# 08_DDR3L_Modules.net
KiCad netlist of a schematic drawn in Altium Designer
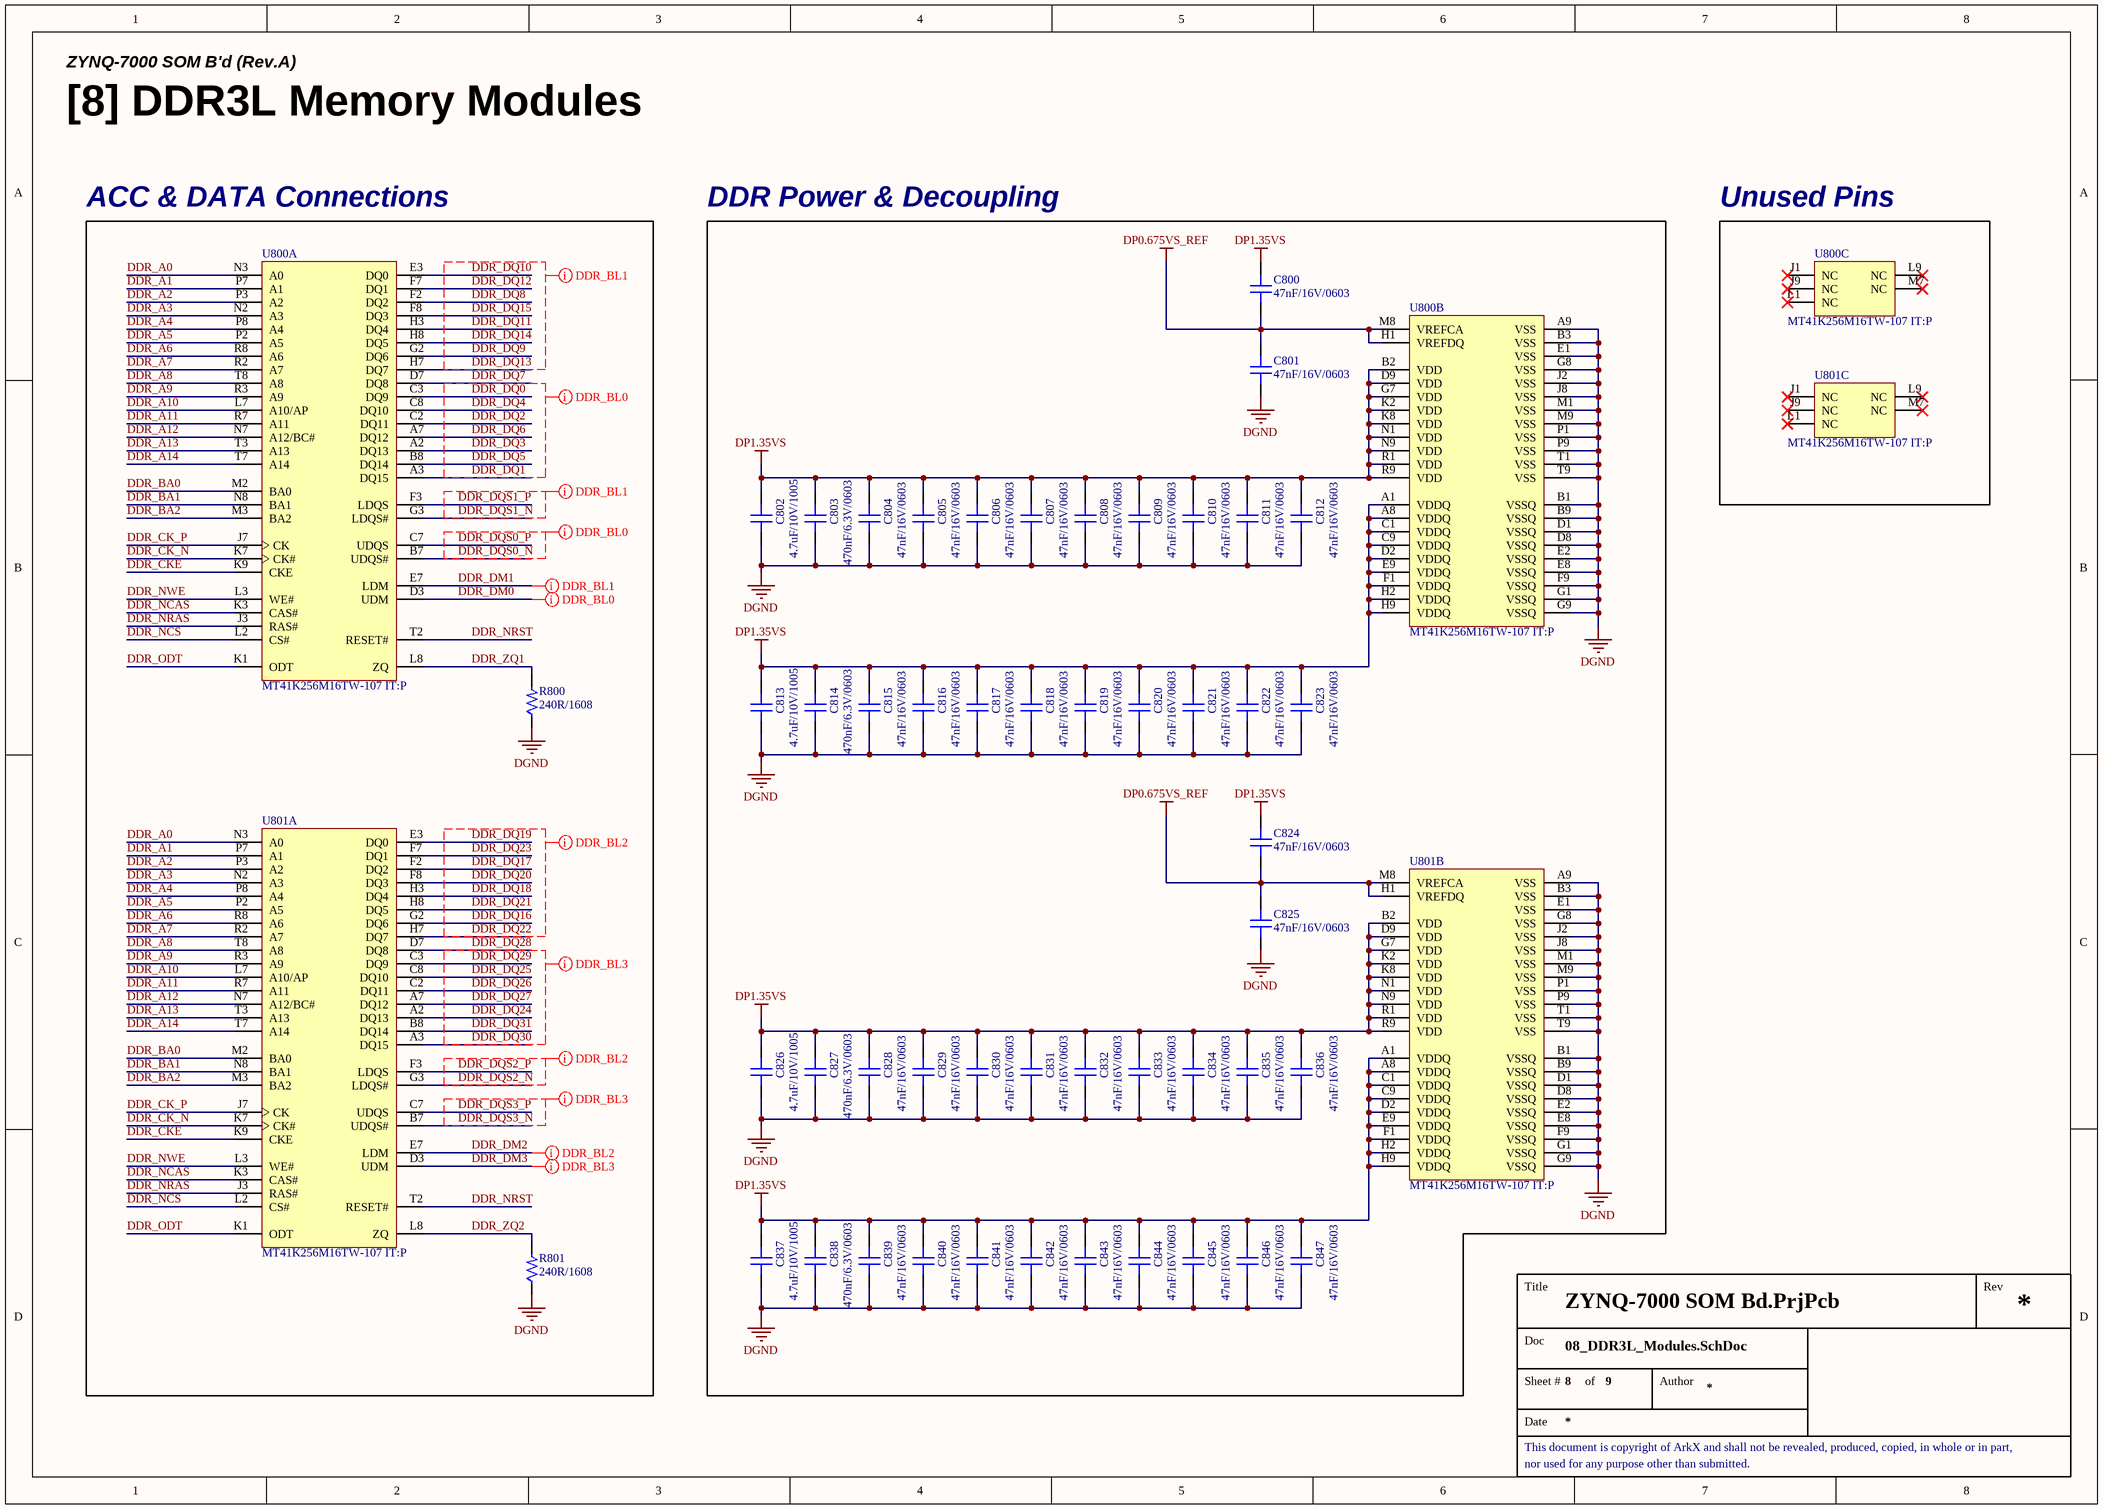
[diagram p0: 08_DDR3L_Modules.SchDoc]

(export (version "E")
  (design (tool "Eeschema 10.0.6"))
  (components
    (comp (ref "C800")
      (value "47nF/16V/0603")
      (footprint "CAP 0603 (0201_INCH)")
      (description "16V 47nF X5R ±10% 0201 Multilayer Ceramic Capacitors MLCC - SMD/SMT ROHS")
      (fields (field (name "LCSC PART #") "C88917"))
      (libsource (lib "Arkx") (part "CAP_47nF/16V/0603"))
    )
    (comp (ref "C801")
      (value "47nF/16V/0603")
      (footprint "CAP 0603 (0201_INCH)")
      (description "16V 47nF X5R ±10% 0201 Multilayer Ceramic Capacitors MLCC - SMD/SMT ROHS")
      (fields (field (name "LCSC PART #") "C88917"))
      (libsource (lib "Arkx") (part "CAP_47nF/16V/0603"))
    )
    (comp (ref "C802")
      (value "4.7uF/10V/1005")
      (footprint "CAP 1005 (0402_INCH)")
      (description "10V 4.7uF X5R ±20% 0402  Multilayer Ceramic Capacitors MLCC - SMD/SMT ROHS")
      (fields (field (name "LCSC PART #") "C23733"))
      (libsource (lib "Arkx") (part "CAP_4.7uF/10V/1005"))
    )
    (comp (ref "C803")
      (value "470nF/6.3V/0603")
      (footprint "CAP 0603 (0201_INCH)")
      (description "6.3V 470nF X5R ±10% 0201  Multilayer Ceramic Capacitors MLCC - SMD/SMT ROHS")
      (fields (field (name "LCSC PART #") "C85926"))
      (libsource (lib "Arkx") (part "CAP_470nF/6.3V/0603"))
    )
    (comp (ref "C804")
      (value "47nF/16V/0603")
      (footprint "CAP 0603 (0201_INCH)")
      (description "16V 47nF X5R ±10% 0201 Multilayer Ceramic Capacitors MLCC - SMD/SMT ROHS")
      (fields (field (name "LCSC PART #") "C88917"))
      (libsource (lib "Arkx") (part "CAP_47nF/16V/0603"))
    )
    (comp (ref "C805")
      (value "47nF/16V/0603")
      (footprint "CAP 0603 (0201_INCH)")
      (description "16V 47nF X5R ±10% 0201 Multilayer Ceramic Capacitors MLCC - SMD/SMT ROHS")
      (fields (field (name "LCSC PART #") "C88917"))
      (libsource (lib "Arkx") (part "CAP_47nF/16V/0603"))
    )
    (comp (ref "C806")
      (value "47nF/16V/0603")
      (footprint "CAP 0603 (0201_INCH)")
      (description "16V 47nF X5R ±10% 0201 Multilayer Ceramic Capacitors MLCC - SMD/SMT ROHS")
      (fields (field (name "LCSC PART #") "C88917"))
      (libsource (lib "Arkx") (part "CAP_47nF/16V/0603"))
    )
    (comp (ref "C807")
      (value "47nF/16V/0603")
      (footprint "CAP 0603 (0201_INCH)")
      (description "16V 47nF X5R ±10% 0201 Multilayer Ceramic Capacitors MLCC - SMD/SMT ROHS")
      (fields (field (name "LCSC PART #") "C88917"))
      (libsource (lib "Arkx") (part "CAP_47nF/16V/0603"))
    )
    (comp (ref "C808")
      (value "47nF/16V/0603")
      (footprint "CAP 0603 (0201_INCH)")
      (description "16V 47nF X5R ±10% 0201 Multilayer Ceramic Capacitors MLCC - SMD/SMT ROHS")
      (fields (field (name "LCSC PART #") "C88917"))
      (libsource (lib "Arkx") (part "CAP_47nF/16V/0603"))
    )
    (comp (ref "C809")
      (value "47nF/16V/0603")
      (footprint "CAP 0603 (0201_INCH)")
      (description "16V 47nF X5R ±10% 0201 Multilayer Ceramic Capacitors MLCC - SMD/SMT ROHS")
      (fields (field (name "LCSC PART #") "C88917"))
      (libsource (lib "Arkx") (part "CAP_47nF/16V/0603"))
    )
    (comp (ref "C810")
      (value "47nF/16V/0603")
      (footprint "CAP 0603 (0201_INCH)")
      (description "16V 47nF X5R ±10% 0201 Multilayer Ceramic Capacitors MLCC - SMD/SMT ROHS")
      (fields (field (name "LCSC PART #") "C88917"))
      (libsource (lib "Arkx") (part "CAP_47nF/16V/0603"))
    )
    (comp (ref "C811")
      (value "47nF/16V/0603")
      (footprint "CAP 0603 (0201_INCH)")
      (description "16V 47nF X5R ±10% 0201 Multilayer Ceramic Capacitors MLCC - SMD/SMT ROHS")
      (fields (field (name "LCSC PART #") "C88917"))
      (libsource (lib "Arkx") (part "CAP_47nF/16V/0603"))
    )
    (comp (ref "C812")
      (value "47nF/16V/0603")
      (footprint "CAP 0603 (0201_INCH)")
      (description "16V 47nF X5R ±10% 0201 Multilayer Ceramic Capacitors MLCC - SMD/SMT ROHS")
      (fields (field (name "LCSC PART #") "C88917"))
      (libsource (lib "Arkx") (part "CAP_47nF/16V/0603"))
    )
    (comp (ref "C813")
      (value "4.7uF/10V/1005")
      (footprint "CAP 1005 (0402_INCH)")
      (description "10V 4.7uF X5R ±20% 0402  Multilayer Ceramic Capacitors MLCC - SMD/SMT ROHS")
      (fields (field (name "LCSC PART #") "C23733"))
      (libsource (lib "Arkx") (part "CAP_4.7uF/10V/1005"))
    )
    (comp (ref "C814")
      (value "470nF/6.3V/0603")
      (footprint "CAP 0603 (0201_INCH)")
      (description "6.3V 470nF X5R ±10% 0201  Multilayer Ceramic Capacitors MLCC - SMD/SMT ROHS")
      (fields (field (name "LCSC PART #") "C85926"))
      (libsource (lib "Arkx") (part "CAP_470nF/6.3V/0603"))
    )
    (comp (ref "C815")
      (value "47nF/16V/0603")
      (footprint "CAP 0603 (0201_INCH)")
      (description "16V 47nF X5R ±10% 0201 Multilayer Ceramic Capacitors MLCC - SMD/SMT ROHS")
      (fields (field (name "LCSC PART #") "C88917"))
      (libsource (lib "Arkx") (part "CAP_47nF/16V/0603"))
    )
    (comp (ref "C816")
      (value "47nF/16V/0603")
      (footprint "CAP 0603 (0201_INCH)")
      (description "16V 47nF X5R ±10% 0201 Multilayer Ceramic Capacitors MLCC - SMD/SMT ROHS")
      (fields (field (name "LCSC PART #") "C88917"))
      (libsource (lib "Arkx") (part "CAP_47nF/16V/0603"))
    )
    (comp (ref "C817")
      (value "47nF/16V/0603")
      (footprint "CAP 0603 (0201_INCH)")
      (description "16V 47nF X5R ±10% 0201 Multilayer Ceramic Capacitors MLCC - SMD/SMT ROHS")
      (fields (field (name "LCSC PART #") "C88917"))
      (libsource (lib "Arkx") (part "CAP_47nF/16V/0603"))
    )
    (comp (ref "C818")
      (value "47nF/16V/0603")
      (footprint "CAP 0603 (0201_INCH)")
      (description "16V 47nF X5R ±10% 0201 Multilayer Ceramic Capacitors MLCC - SMD/SMT ROHS")
      (fields (field (name "LCSC PART #") "C88917"))
      (libsource (lib "Arkx") (part "CAP_47nF/16V/0603"))
    )
    (comp (ref "C819")
      (value "47nF/16V/0603")
      (footprint "CAP 0603 (0201_INCH)")
      (description "16V 47nF X5R ±10% 0201 Multilayer Ceramic Capacitors MLCC - SMD/SMT ROHS")
      (fields (field (name "LCSC PART #") "C88917"))
      (libsource (lib "Arkx") (part "CAP_47nF/16V/0603"))
    )
    (comp (ref "C820")
      (value "47nF/16V/0603")
      (footprint "CAP 0603 (0201_INCH)")
      (description "16V 47nF X5R ±10% 0201 Multilayer Ceramic Capacitors MLCC - SMD/SMT ROHS")
      (fields (field (name "LCSC PART #") "C88917"))
      (libsource (lib "Arkx") (part "CAP_47nF/16V/0603"))
    )
    (comp (ref "C821")
      (value "47nF/16V/0603")
      (footprint "CAP 0603 (0201_INCH)")
      (description "16V 47nF X5R ±10% 0201 Multilayer Ceramic Capacitors MLCC - SMD/SMT ROHS")
      (fields (field (name "LCSC PART #") "C88917"))
      (libsource (lib "Arkx") (part "CAP_47nF/16V/0603"))
    )
    (comp (ref "C822")
      (value "47nF/16V/0603")
      (footprint "CAP 0603 (0201_INCH)")
      (description "16V 47nF X5R ±10% 0201 Multilayer Ceramic Capacitors MLCC - SMD/SMT ROHS")
      (fields (field (name "LCSC PART #") "C88917"))
      (libsource (lib "Arkx") (part "CAP_47nF/16V/0603"))
    )
    (comp (ref "C823")
      (value "47nF/16V/0603")
      (footprint "CAP 0603 (0201_INCH)")
      (description "16V 47nF X5R ±10% 0201 Multilayer Ceramic Capacitors MLCC - SMD/SMT ROHS")
      (fields (field (name "LCSC PART #") "C88917"))
      (libsource (lib "Arkx") (part "CAP_47nF/16V/0603"))
    )
    (comp (ref "C824")
      (value "47nF/16V/0603")
      (footprint "CAP 0603 (0201_INCH)")
      (description "16V 47nF X5R ±10% 0201 Multilayer Ceramic Capacitors MLCC - SMD/SMT ROHS")
      (fields (field (name "LCSC PART #") "C88917"))
      (libsource (lib "Arkx") (part "CAP_47nF/16V/0603"))
    )
    (comp (ref "C825")
      (value "47nF/16V/0603")
      (footprint "CAP 0603 (0201_INCH)")
      (description "16V 47nF X5R ±10% 0201 Multilayer Ceramic Capacitors MLCC - SMD/SMT ROHS")
      (fields (field (name "LCSC PART #") "C88917"))
      (libsource (lib "Arkx") (part "CAP_47nF/16V/0603"))
    )
    (comp (ref "C826")
      (value "4.7uF/10V/1005")
      (footprint "CAP 1005 (0402_INCH)")
      (description "10V 4.7uF X5R ±20% 0402  Multilayer Ceramic Capacitors MLCC - SMD/SMT ROHS")
      (fields (field (name "LCSC PART #") "C23733"))
      (libsource (lib "Arkx") (part "CAP_4.7uF/10V/1005"))
    )
    (comp (ref "C827")
      (value "470nF/6.3V/0603")
      (footprint "CAP 0603 (0201_INCH)")
      (description "6.3V 470nF X5R ±10% 0201  Multilayer Ceramic Capacitors MLCC - SMD/SMT ROHS")
      (fields (field (name "LCSC PART #") "C85926"))
      (libsource (lib "Arkx") (part "CAP_470nF/6.3V/0603"))
    )
    (comp (ref "C828")
      (value "47nF/16V/0603")
      (footprint "CAP 0603 (0201_INCH)")
      (description "16V 47nF X5R ±10% 0201 Multilayer Ceramic Capacitors MLCC - SMD/SMT ROHS")
      (fields (field (name "LCSC PART #") "C88917"))
      (libsource (lib "Arkx") (part "CAP_47nF/16V/0603"))
    )
    (comp (ref "C829")
      (value "47nF/16V/0603")
      (footprint "CAP 0603 (0201_INCH)")
      (description "16V 47nF X5R ±10% 0201 Multilayer Ceramic Capacitors MLCC - SMD/SMT ROHS")
      (fields (field (name "LCSC PART #") "C88917"))
      (libsource (lib "Arkx") (part "CAP_47nF/16V/0603"))
    )
    (comp (ref "C830")
      (value "47nF/16V/0603")
      (footprint "CAP 0603 (0201_INCH)")
      (description "16V 47nF X5R ±10% 0201 Multilayer Ceramic Capacitors MLCC - SMD/SMT ROHS")
      (fields (field (name "LCSC PART #") "C88917"))
      (libsource (lib "Arkx") (part "CAP_47nF/16V/0603"))
    )
    (comp (ref "C831")
      (value "47nF/16V/0603")
      (footprint "CAP 0603 (0201_INCH)")
      (description "16V 47nF X5R ±10% 0201 Multilayer Ceramic Capacitors MLCC - SMD/SMT ROHS")
      (fields (field (name "LCSC PART #") "C88917"))
      (libsource (lib "Arkx") (part "CAP_47nF/16V/0603"))
    )
    (comp (ref "C832")
      (value "47nF/16V/0603")
      (footprint "CAP 0603 (0201_INCH)")
      (description "16V 47nF X5R ±10% 0201 Multilayer Ceramic Capacitors MLCC - SMD/SMT ROHS")
      (fields (field (name "LCSC PART #") "C88917"))
      (libsource (lib "Arkx") (part "CAP_47nF/16V/0603"))
    )
    (comp (ref "C833")
      (value "47nF/16V/0603")
      (footprint "CAP 0603 (0201_INCH)")
      (description "16V 47nF X5R ±10% 0201 Multilayer Ceramic Capacitors MLCC - SMD/SMT ROHS")
      (fields (field (name "LCSC PART #") "C88917"))
      (libsource (lib "Arkx") (part "CAP_47nF/16V/0603"))
    )
    (comp (ref "C834")
      (value "47nF/16V/0603")
      (footprint "CAP 0603 (0201_INCH)")
      (description "16V 47nF X5R ±10% 0201 Multilayer Ceramic Capacitors MLCC - SMD/SMT ROHS")
      (fields (field (name "LCSC PART #") "C88917"))
      (libsource (lib "Arkx") (part "CAP_47nF/16V/0603"))
    )
    (comp (ref "C835")
      (value "47nF/16V/0603")
      (footprint "CAP 0603 (0201_INCH)")
      (description "16V 47nF X5R ±10% 0201 Multilayer Ceramic Capacitors MLCC - SMD/SMT ROHS")
      (fields (field (name "LCSC PART #") "C88917"))
      (libsource (lib "Arkx") (part "CAP_47nF/16V/0603"))
    )
    (comp (ref "C836")
      (value "47nF/16V/0603")
      (footprint "CAP 0603 (0201_INCH)")
      (description "16V 47nF X5R ±10% 0201 Multilayer Ceramic Capacitors MLCC - SMD/SMT ROHS")
      (fields (field (name "LCSC PART #") "C88917"))
      (libsource (lib "Arkx") (part "CAP_47nF/16V/0603"))
    )
    (comp (ref "C837")
      (value "4.7uF/10V/1005")
      (footprint "CAP 1005 (0402_INCH)")
      (description "10V 4.7uF X5R ±20% 0402  Multilayer Ceramic Capacitors MLCC - SMD/SMT ROHS")
      (fields (field (name "LCSC PART #") "C23733"))
      (libsource (lib "Arkx") (part "CAP_4.7uF/10V/1005"))
    )
    (comp (ref "C838")
      (value "470nF/6.3V/0603")
      (footprint "CAP 0603 (0201_INCH)")
      (description "6.3V 470nF X5R ±10% 0201  Multilayer Ceramic Capacitors MLCC - SMD/SMT ROHS")
      (fields (field (name "LCSC PART #") "C85926"))
      (libsource (lib "Arkx") (part "CAP_470nF/6.3V/0603"))
    )
    (comp (ref "C839")
      (value "47nF/16V/0603")
      (footprint "CAP 0603 (0201_INCH)")
      (description "16V 47nF X5R ±10% 0201 Multilayer Ceramic Capacitors MLCC - SMD/SMT ROHS")
      (fields (field (name "LCSC PART #") "C88917"))
      (libsource (lib "Arkx") (part "CAP_47nF/16V/0603"))
    )
    (comp (ref "C840")
      (value "47nF/16V/0603")
      (footprint "CAP 0603 (0201_INCH)")
      (description "16V 47nF X5R ±10% 0201 Multilayer Ceramic Capacitors MLCC - SMD/SMT ROHS")
      (fields (field (name "LCSC PART #") "C88917"))
      (libsource (lib "Arkx") (part "CAP_47nF/16V/0603"))
    )
    (comp (ref "C841")
      (value "47nF/16V/0603")
      (footprint "CAP 0603 (0201_INCH)")
      (description "16V 47nF X5R ±10% 0201 Multilayer Ceramic Capacitors MLCC - SMD/SMT ROHS")
      (fields (field (name "LCSC PART #") "C88917"))
      (libsource (lib "Arkx") (part "CAP_47nF/16V/0603"))
    )
    (comp (ref "C842")
      (value "47nF/16V/0603")
      (footprint "CAP 0603 (0201_INCH)")
      (description "16V 47nF X5R ±10% 0201 Multilayer Ceramic Capacitors MLCC - SMD/SMT ROHS")
      (fields (field (name "LCSC PART #") "C88917"))
      (libsource (lib "Arkx") (part "CAP_47nF/16V/0603"))
    )
    (comp (ref "C843")
      (value "47nF/16V/0603")
      (footprint "CAP 0603 (0201_INCH)")
      (description "16V 47nF X5R ±10% 0201 Multilayer Ceramic Capacitors MLCC - SMD/SMT ROHS")
      (fields (field (name "LCSC PART #") "C88917"))
      (libsource (lib "Arkx") (part "CAP_47nF/16V/0603"))
    )
    (comp (ref "C844")
      (value "47nF/16V/0603")
      (footprint "CAP 0603 (0201_INCH)")
      (description "16V 47nF X5R ±10% 0201 Multilayer Ceramic Capacitors MLCC - SMD/SMT ROHS")
      (fields (field (name "LCSC PART #") "C88917"))
      (libsource (lib "Arkx") (part "CAP_47nF/16V/0603"))
    )
    (comp (ref "C845")
      (value "47nF/16V/0603")
      (footprint "CAP 0603 (0201_INCH)")
      (description "16V 47nF X5R ±10% 0201 Multilayer Ceramic Capacitors MLCC - SMD/SMT ROHS")
      (fields (field (name "LCSC PART #") "C88917"))
      (libsource (lib "Arkx") (part "CAP_47nF/16V/0603"))
    )
    (comp (ref "C846")
      (value "47nF/16V/0603")
      (footprint "CAP 0603 (0201_INCH)")
      (description "16V 47nF X5R ±10% 0201 Multilayer Ceramic Capacitors MLCC - SMD/SMT ROHS")
      (fields (field (name "LCSC PART #") "C88917"))
      (libsource (lib "Arkx") (part "CAP_47nF/16V/0603"))
    )
    (comp (ref "C847")
      (value "47nF/16V/0603")
      (footprint "CAP 0603 (0201_INCH)")
      (description "16V 47nF X5R ±10% 0201 Multilayer Ceramic Capacitors MLCC - SMD/SMT ROHS")
      (fields (field (name "LCSC PART #") "C88917"))
      (libsource (lib "Arkx") (part "CAP_47nF/16V/0603"))
    )
    (comp (ref "R800")
      (value "240R/1608")
      (footprint "RES 1608 (0603_inch)")
      (description "RES_240R/1608/0.1W")
      (fields (field (name "LCSC PART #") "C23350"))
      (libsource (lib "Arkx") (part "RES_240R/1608/0.1W"))
    )
    (comp (ref "R801")
      (value "240R/1608")
      (footprint "RES 1608 (0603_inch)")
      (description "RES_240R/1608/0.1W")
      (fields (field (name "LCSC PART #") "C23350"))
      (libsource (lib "Arkx") (part "RES_240R/1608/0.1W"))
    )
    (comp (ref "U800")
      (value "MT41K256M16TW-107 IT:P")
      (footprint "IC_MEM_DDR3L_MT41K256M16TW-107 IT:P")
      (description "SDRAM - DDR3L Memory IC 4Gbit Parallel 933 MHz 20 ns 96-FBGA (8x14)")
      (fields (field (name "LCSC PART #") "C367428"))
      (libsource (lib "Arkx") (part "IC_MEM_DDR3L_MT41K256M16TW-107 IT{colon}P"))
    )
    (comp (ref "U801")
      (value "MT41K256M16TW-107 IT:P")
      (footprint "IC_MEM_DDR3L_MT41K256M16TW-107 IT:P")
      (description "SDRAM - DDR3L Memory IC 4Gbit Parallel 933 MHz 20 ns 96-FBGA (8x14)")
      (fields (field (name "LCSC PART #") "C367428"))
      (libsource (lib "Arkx") (part "IC_MEM_DDR3L_MT41K256M16TW-107 IT{colon}P"))
    )
  )
  (nets
    (net (code "1") (name "/DDR_A0") (class "Default")
      (node (ref "U800") (pin "N3") (pinfunction "A0_N3") (pintype "passive"))
      (node (ref "U801") (pin "N3") (pinfunction "A0_N3") (pintype "passive"))
    )
    (net (code "2") (name "/DDR_A1") (class "Default")
      (node (ref "U800") (pin "P7") (pinfunction "A1_P7") (pintype "passive"))
      (node (ref "U801") (pin "P7") (pinfunction "A1_P7") (pintype "passive"))
    )
    (net (code "3") (name "/DDR_A2") (class "Default")
      (node (ref "U800") (pin "P3") (pinfunction "A2_P3") (pintype "passive"))
      (node (ref "U801") (pin "P3") (pinfunction "A2_P3") (pintype "passive"))
    )
    (net (code "4") (name "/DDR_A3") (class "Default")
      (node (ref "U800") (pin "N2") (pinfunction "A3_N2") (pintype "passive"))
      (node (ref "U801") (pin "N2") (pinfunction "A3_N2") (pintype "passive"))
    )
    (net (code "5") (name "/DDR_A4") (class "Default")
      (node (ref "U800") (pin "P8") (pinfunction "A4_P8") (pintype "passive"))
      (node (ref "U801") (pin "P8") (pinfunction "A4_P8") (pintype "passive"))
    )
    (net (code "6") (name "/DDR_A5") (class "Default")
      (node (ref "U800") (pin "P2") (pinfunction "A5_P2") (pintype "passive"))
      (node (ref "U801") (pin "P2") (pinfunction "A5_P2") (pintype "passive"))
    )
    (net (code "7") (name "/DDR_A6") (class "Default")
      (node (ref "U800") (pin "R8") (pinfunction "A6_R8") (pintype "passive"))
      (node (ref "U801") (pin "R8") (pinfunction "A6_R8") (pintype "passive"))
    )
    (net (code "8") (name "/DDR_A7") (class "Default")
      (node (ref "U800") (pin "R2") (pinfunction "A7_R2") (pintype "passive"))
      (node (ref "U801") (pin "R2") (pinfunction "A7_R2") (pintype "passive"))
    )
    (net (code "9") (name "/DDR_A8") (class "Default")
      (node (ref "U800") (pin "T8") (pinfunction "A8_T8") (pintype "passive"))
      (node (ref "U801") (pin "T8") (pinfunction "A8_T8") (pintype "passive"))
    )
    (net (code "10") (name "/DDR_A9") (class "Default")
      (node (ref "U800") (pin "R3") (pinfunction "A9_R3") (pintype "passive"))
      (node (ref "U801") (pin "R3") (pinfunction "A9_R3") (pintype "passive"))
    )
    (net (code "11") (name "/DDR_A10") (class "Default")
      (node (ref "U800") (pin "L7") (pinfunction "A10/AP_L7") (pintype "passive"))
      (node (ref "U801") (pin "L7") (pinfunction "A10/AP_L7") (pintype "passive"))
    )
    (net (code "12") (name "/DDR_A11") (class "Default")
      (node (ref "U800") (pin "R7") (pinfunction "A11_R7") (pintype "passive"))
      (node (ref "U801") (pin "R7") (pinfunction "A11_R7") (pintype "passive"))
    )
    (net (code "13") (name "/DDR_A12") (class "Default")
      (node (ref "U800") (pin "N7") (pinfunction "A12/BC#_N7") (pintype "passive"))
      (node (ref "U801") (pin "N7") (pinfunction "A12/BC#_N7") (pintype "passive"))
    )
    (net (code "14") (name "/DDR_A13") (class "Default")
      (node (ref "U800") (pin "T3") (pinfunction "A13_T3") (pintype "passive"))
      (node (ref "U801") (pin "T3") (pinfunction "A13_T3") (pintype "passive"))
    )
    (net (code "15") (name "/DDR_A14") (class "Default")
      (node (ref "U800") (pin "T7") (pinfunction "A14_T7") (pintype "passive"))
      (node (ref "U801") (pin "T7") (pinfunction "A14_T7") (pintype "passive"))
    )
    (net (code "16") (name "/DDR_BA0") (class "Default")
      (node (ref "U800") (pin "M2") (pinfunction "BA0_M2") (pintype "passive"))
      (node (ref "U801") (pin "M2") (pinfunction "BA0_M2") (pintype "passive"))
    )
    (net (code "17") (name "/DDR_BA1") (class "Default")
      (node (ref "U800") (pin "N8") (pinfunction "BA1_N8") (pintype "passive"))
      (node (ref "U801") (pin "N8") (pinfunction "BA1_N8") (pintype "passive"))
    )
    (net (code "18") (name "/DDR_BA2") (class "Default")
      (node (ref "U800") (pin "M3") (pinfunction "BA2_M3") (pintype "passive"))
      (node (ref "U801") (pin "M3") (pinfunction "BA2_M3") (pintype "passive"))
    )
    (net (code "19") (name "/DDR_CKE") (class "Default")
      (node (ref "U800") (pin "K9") (pinfunction "CKE_K9") (pintype "passive"))
      (node (ref "U801") (pin "K9") (pinfunction "CKE_K9") (pintype "passive"))
    )
    (net (code "20") (name "/DDR_CK_N") (class "Default")
      (node (ref "U800") (pin "K7") (pinfunction "CK#_K7") (pintype "passive"))
      (node (ref "U801") (pin "K7") (pinfunction "CK#_K7") (pintype "passive"))
    )
    (net (code "21") (name "/DDR_CK_P") (class "Default")
      (node (ref "U800") (pin "J7") (pinfunction "CK_J7") (pintype "passive"))
      (node (ref "U801") (pin "J7") (pinfunction "CK_J7") (pintype "passive"))
    )
    (net (code "22") (name "/DDR_DM0") (class "Default")
      (node (ref "U800") (pin "D3") (pinfunction "UDM_D3") (pintype "passive"))
    )
    (net (code "23") (name "/DDR_DM1") (class "Default")
      (node (ref "U800") (pin "E7") (pinfunction "LDM_E7") (pintype "passive"))
    )
    (net (code "24") (name "/DDR_DM2") (class "Default")
      (node (ref "U801") (pin "E7") (pinfunction "LDM_E7") (pintype "passive"))
    )
    (net (code "25") (name "/DDR_DM3") (class "Default")
      (node (ref "U801") (pin "D3") (pinfunction "UDM_D3") (pintype "passive"))
    )
    (net (code "26") (name "/DDR_DQ0") (class "Default")
      (node (ref "U800") (pin "C3") (pinfunction "DQ9_C3") (pintype "passive"))
    )
    (net (code "27") (name "/DDR_DQ1") (class "Default")
      (node (ref "U800") (pin "A3") (pinfunction "DQ15_A3") (pintype "passive"))
    )
    (net (code "28") (name "/DDR_DQ2") (class "Default")
      (node (ref "U800") (pin "C2") (pinfunction "DQ11_C2") (pintype "passive"))
    )
    (net (code "29") (name "/DDR_DQ3") (class "Default")
      (node (ref "U800") (pin "A2") (pinfunction "DQ13_A2") (pintype "passive"))
    )
    (net (code "30") (name "/DDR_DQ4") (class "Default")
      (node (ref "U800") (pin "C8") (pinfunction "DQ10_C8") (pintype "passive"))
    )
    (net (code "31") (name "/DDR_DQ5") (class "Default")
      (node (ref "U800") (pin "B8") (pinfunction "DQ14_B8") (pintype "passive"))
    )
    (net (code "32") (name "/DDR_DQ6") (class "Default")
      (node (ref "U800") (pin "A7") (pinfunction "DQ12_A7") (pintype "passive"))
    )
    (net (code "33") (name "/DDR_DQ7") (class "Default")
      (node (ref "U800") (pin "D7") (pinfunction "DQ8_D7") (pintype "passive"))
    )
    (net (code "34") (name "/DDR_DQ8") (class "Default")
      (node (ref "U800") (pin "F2") (pinfunction "DQ2_F2") (pintype "passive"))
    )
    (net (code "35") (name "/DDR_DQ9") (class "Default")
      (node (ref "U800") (pin "G2") (pinfunction "DQ6_G2") (pintype "passive"))
    )
    (net (code "36") (name "/DDR_DQ10") (class "Default")
      (node (ref "U800") (pin "E3") (pinfunction "DQ0_E3") (pintype "passive"))
    )
    (net (code "37") (name "/DDR_DQ11") (class "Default")
      (node (ref "U800") (pin "H3") (pinfunction "DQ4_H3") (pintype "passive"))
    )
    (net (code "38") (name "/DDR_DQ12") (class "Default")
      (node (ref "U800") (pin "F7") (pinfunction "DQ1_F7") (pintype "passive"))
    )
    (net (code "39") (name "/DDR_DQ13") (class "Default")
      (node (ref "U800") (pin "H7") (pinfunction "DQ7_H7") (pintype "passive"))
    )
    (net (code "40") (name "/DDR_DQ14") (class "Default")
      (node (ref "U800") (pin "H8") (pinfunction "DQ5_H8") (pintype "passive"))
    )
    (net (code "41") (name "/DDR_DQ15") (class "Default")
      (node (ref "U800") (pin "F8") (pinfunction "DQ3_F8") (pintype "passive"))
    )
    (net (code "42") (name "/DDR_DQ16") (class "Default")
      (node (ref "U801") (pin "G2") (pinfunction "DQ6_G2") (pintype "passive"))
    )
    (net (code "43") (name "/DDR_DQ17") (class "Default")
      (node (ref "U801") (pin "F2") (pinfunction "DQ2_F2") (pintype "passive"))
    )
    (net (code "44") (name "/DDR_DQ18") (class "Default")
      (node (ref "U801") (pin "H3") (pinfunction "DQ4_H3") (pintype "passive"))
    )
    (net (code "45") (name "/DDR_DQ19") (class "Default")
      (node (ref "U801") (pin "E3") (pinfunction "DQ0_E3") (pintype "passive"))
    )
    (net (code "46") (name "/DDR_DQ20") (class "Default")
      (node (ref "U801") (pin "F8") (pinfunction "DQ3_F8") (pintype "passive"))
    )
    (net (code "47") (name "/DDR_DQ21") (class "Default")
      (node (ref "U801") (pin "H8") (pinfunction "DQ5_H8") (pintype "passive"))
    )
    (net (code "48") (name "/DDR_DQ22") (class "Default")
      (node (ref "U801") (pin "H7") (pinfunction "DQ7_H7") (pintype "passive"))
    )
    (net (code "49") (name "/DDR_DQ23") (class "Default")
      (node (ref "U801") (pin "F7") (pinfunction "DQ1_F7") (pintype "passive"))
    )
    (net (code "50") (name "/DDR_DQ24") (class "Default")
      (node (ref "U801") (pin "A2") (pinfunction "DQ13_A2") (pintype "passive"))
    )
    (net (code "51") (name "/DDR_DQ25") (class "Default")
      (node (ref "U801") (pin "C8") (pinfunction "DQ10_C8") (pintype "passive"))
    )
    (net (code "52") (name "/DDR_DQ26") (class "Default")
      (node (ref "U801") (pin "C2") (pinfunction "DQ11_C2") (pintype "passive"))
    )
    (net (code "53") (name "/DDR_DQ27") (class "Default")
      (node (ref "U801") (pin "A7") (pinfunction "DQ12_A7") (pintype "passive"))
    )
    (net (code "54") (name "/DDR_DQ28") (class "Default")
      (node (ref "U801") (pin "D7") (pinfunction "DQ8_D7") (pintype "passive"))
    )
    (net (code "55") (name "/DDR_DQ29") (class "Default")
      (node (ref "U801") (pin "C3") (pinfunction "DQ9_C3") (pintype "passive"))
    )
    (net (code "56") (name "/DDR_DQ30") (class "Default")
      (node (ref "U801") (pin "A3") (pinfunction "DQ15_A3") (pintype "passive"))
    )
    (net (code "57") (name "/DDR_DQ31") (class "Default")
      (node (ref "U801") (pin "B8") (pinfunction "DQ14_B8") (pintype "passive"))
    )
    (net (code "58") (name "/DDR_DQS0_N") (class "Default")
      (node (ref "U800") (pin "B7") (pinfunction "UDQS#_B7") (pintype "passive"))
    )
    (net (code "59") (name "/DDR_DQS0_P") (class "Default")
      (node (ref "U800") (pin "C7") (pinfunction "UDQS_C7") (pintype "passive"))
    )
    (net (code "60") (name "/DDR_DQS1_N") (class "Default")
      (node (ref "U800") (pin "G3") (pinfunction "LDQS#_G3") (pintype "passive"))
    )
    (net (code "61") (name "/DDR_DQS1_P") (class "Default")
      (node (ref "U800") (pin "F3") (pinfunction "LDQS_F3") (pintype "passive"))
    )
    (net (code "62") (name "/DDR_DQS2_N") (class "Default")
      (node (ref "U801") (pin "G3") (pinfunction "LDQS#_G3") (pintype "passive"))
    )
    (net (code "63") (name "/DDR_DQS2_P") (class "Default")
      (node (ref "U801") (pin "F3") (pinfunction "LDQS_F3") (pintype "passive"))
    )
    (net (code "64") (name "/DDR_DQS3_N") (class "Default")
      (node (ref "U801") (pin "B7") (pinfunction "UDQS#_B7") (pintype "passive"))
    )
    (net (code "65") (name "/DDR_DQS3_P") (class "Default")
      (node (ref "U801") (pin "C7") (pinfunction "UDQS_C7") (pintype "passive"))
    )
    (net (code "66") (name "/DDR_NCAS") (class "Default")
      (node (ref "U800") (pin "K3") (pinfunction "CAS#_K3") (pintype "passive"))
      (node (ref "U801") (pin "K3") (pinfunction "CAS#_K3") (pintype "passive"))
    )
    (net (code "67") (name "/DDR_NCS") (class "Default")
      (node (ref "U800") (pin "L2") (pinfunction "CS#_L2") (pintype "passive"))
      (node (ref "U801") (pin "L2") (pinfunction "CS#_L2") (pintype "passive"))
    )
    (net (code "68") (name "/DDR_NRAS") (class "Default")
      (node (ref "U800") (pin "J3") (pinfunction "RAS#_J3") (pintype "passive"))
      (node (ref "U801") (pin "J3") (pinfunction "RAS#_J3") (pintype "passive"))
    )
    (net (code "69") (name "/DDR_NRST") (class "Default")
      (node (ref "U800") (pin "T2") (pinfunction "RESET#_T2") (pintype "passive"))
      (node (ref "U801") (pin "T2") (pinfunction "RESET#_T2") (pintype "passive"))
    )
    (net (code "70") (name "/DDR_NWE") (class "Default")
      (node (ref "U800") (pin "L3") (pinfunction "WE#_L3") (pintype "passive"))
      (node (ref "U801") (pin "L3") (pinfunction "WE#_L3") (pintype "passive"))
    )
    (net (code "71") (name "/DDR_ODT") (class "Default")
      (node (ref "U800") (pin "K1") (pinfunction "ODT_K1") (pintype "passive"))
      (node (ref "U801") (pin "K1") (pinfunction "ODT_K1") (pintype "passive"))
    )
    (net (code "72") (name "/DDR_ZQ1") (class "Default")
      (node (ref "R800") (pin "2") (pinfunction "2_2") (pintype "passive"))
      (node (ref "U800") (pin "L8") (pinfunction "ZQ_L8") (pintype "passive"))
    )
    (net (code "73") (name "/DDR_ZQ2") (class "Default")
      (node (ref "R801") (pin "2") (pinfunction "2_2") (pintype "passive"))
      (node (ref "U801") (pin "L8") (pinfunction "ZQ_L8") (pintype "passive"))
    )
    (net (code "74") (name "DGND") (class "Default")
      (node (ref "C801") (pin "1") (pinfunction "1_1") (pintype "passive"))
      (node (ref "C802") (pin "1") (pinfunction "1_1") (pintype "passive"))
      (node (ref "C803") (pin "1") (pinfunction "1_1") (pintype "passive"))
      (node (ref "C804") (pin "1") (pinfunction "1_1") (pintype "passive"))
      (node (ref "C805") (pin "1") (pinfunction "1_1") (pintype "passive"))
      (node (ref "C806") (pin "1") (pinfunction "1_1") (pintype "passive"))
      (node (ref "C807") (pin "1") (pinfunction "1_1") (pintype "passive"))
      (node (ref "C808") (pin "1") (pinfunction "1_1") (pintype "passive"))
      (node (ref "C809") (pin "1") (pinfunction "1_1") (pintype "passive"))
      (node (ref "C810") (pin "1") (pinfunction "1_1") (pintype "passive"))
      (node (ref "C811") (pin "1") (pinfunction "1_1") (pintype "passive"))
      (node (ref "C812") (pin "1") (pinfunction "1_1") (pintype "passive"))
      (node (ref "C813") (pin "1") (pinfunction "1_1") (pintype "passive"))
      (node (ref "C814") (pin "1") (pinfunction "1_1") (pintype "passive"))
      (node (ref "C815") (pin "1") (pinfunction "1_1") (pintype "passive"))
      (node (ref "C816") (pin "1") (pinfunction "1_1") (pintype "passive"))
      (node (ref "C817") (pin "1") (pinfunction "1_1") (pintype "passive"))
      (node (ref "C818") (pin "1") (pinfunction "1_1") (pintype "passive"))
      (node (ref "C819") (pin "1") (pinfunction "1_1") (pintype "passive"))
      (node (ref "C820") (pin "1") (pinfunction "1_1") (pintype "passive"))
      (node (ref "C821") (pin "1") (pinfunction "1_1") (pintype "passive"))
      (node (ref "C822") (pin "1") (pinfunction "1_1") (pintype "passive"))
      (node (ref "C823") (pin "1") (pinfunction "1_1") (pintype "passive"))
      (node (ref "C825") (pin "1") (pinfunction "1_1") (pintype "passive"))
      (node (ref "C826") (pin "1") (pinfunction "1_1") (pintype "passive"))
      (node (ref "C827") (pin "1") (pinfunction "1_1") (pintype "passive"))
      (node (ref "C828") (pin "1") (pinfunction "1_1") (pintype "passive"))
      (node (ref "C829") (pin "1") (pinfunction "1_1") (pintype "passive"))
      (node (ref "C830") (pin "1") (pinfunction "1_1") (pintype "passive"))
      (node (ref "C831") (pin "1") (pinfunction "1_1") (pintype "passive"))
      (node (ref "C832") (pin "1") (pinfunction "1_1") (pintype "passive"))
      (node (ref "C833") (pin "1") (pinfunction "1_1") (pintype "passive"))
      (node (ref "C834") (pin "1") (pinfunction "1_1") (pintype "passive"))
      (node (ref "C835") (pin "1") (pinfunction "1_1") (pintype "passive"))
      (node (ref "C836") (pin "1") (pinfunction "1_1") (pintype "passive"))
      (node (ref "C837") (pin "1") (pinfunction "1_1") (pintype "passive"))
      (node (ref "C838") (pin "1") (pinfunction "1_1") (pintype "passive"))
      (node (ref "C839") (pin "1") (pinfunction "1_1") (pintype "passive"))
      (node (ref "C840") (pin "1") (pinfunction "1_1") (pintype "passive"))
      (node (ref "C841") (pin "1") (pinfunction "1_1") (pintype "passive"))
      (node (ref "C842") (pin "1") (pinfunction "1_1") (pintype "passive"))
      (node (ref "C843") (pin "1") (pinfunction "1_1") (pintype "passive"))
      (node (ref "C844") (pin "1") (pinfunction "1_1") (pintype "passive"))
      (node (ref "C845") (pin "1") (pinfunction "1_1") (pintype "passive"))
      (node (ref "C846") (pin "1") (pinfunction "1_1") (pintype "passive"))
      (node (ref "C847") (pin "1") (pinfunction "1_1") (pintype "passive"))
      (node (ref "R800") (pin "1") (pinfunction "1_1") (pintype "passive"))
      (node (ref "R801") (pin "1") (pinfunction "1_1") (pintype "passive"))
      (node (ref "U800") (pin "A9") (pinfunction "VSS_A9") (pintype "passive"))
      (node (ref "U800") (pin "B1") (pinfunction "VSSQ_B1") (pintype "passive"))
      (node (ref "U800") (pin "B3") (pinfunction "VSS_B3") (pintype "passive"))
      (node (ref "U800") (pin "B9") (pinfunction "VSSQ_B9") (pintype "passive"))
      (node (ref "U800") (pin "D1") (pinfunction "VSSQ_D1") (pintype "passive"))
      (node (ref "U800") (pin "D8") (pinfunction "VSSQ_D8") (pintype "passive"))
      (node (ref "U800") (pin "E1") (pinfunction "VSS_E1") (pintype "passive"))
      (node (ref "U800") (pin "E2") (pinfunction "VSSQ_E2") (pintype "passive"))
      (node (ref "U800") (pin "E8") (pinfunction "VSSQ_E8") (pintype "passive"))
      (node (ref "U800") (pin "F9") (pinfunction "VSSQ_F9") (pintype "passive"))
      (node (ref "U800") (pin "G1") (pinfunction "VSSQ_G1") (pintype "passive"))
      (node (ref "U800") (pin "G8") (pinfunction "VSS_G8") (pintype "passive"))
      (node (ref "U800") (pin "G9") (pinfunction "VSSQ_G9") (pintype "passive"))
      (node (ref "U800") (pin "J2") (pinfunction "VSS_J2") (pintype "passive"))
      (node (ref "U800") (pin "J8") (pinfunction "VSS_J8") (pintype "passive"))
      (node (ref "U800") (pin "M1") (pinfunction "VSS_M1") (pintype "passive"))
      (node (ref "U800") (pin "M9") (pinfunction "VSS_M9") (pintype "passive"))
      (node (ref "U800") (pin "P1") (pinfunction "VSS_P1") (pintype "passive"))
      (node (ref "U800") (pin "P9") (pinfunction "VSS_P9") (pintype "passive"))
      (node (ref "U800") (pin "T1") (pinfunction "VSS_T1") (pintype "passive"))
      (node (ref "U800") (pin "T9") (pinfunction "VSS_T9") (pintype "passive"))
      (node (ref "U801") (pin "A9") (pinfunction "VSS_A9") (pintype "passive"))
      (node (ref "U801") (pin "B1") (pinfunction "VSSQ_B1") (pintype "passive"))
      (node (ref "U801") (pin "B3") (pinfunction "VSS_B3") (pintype "passive"))
      (node (ref "U801") (pin "B9") (pinfunction "VSSQ_B9") (pintype "passive"))
      (node (ref "U801") (pin "D1") (pinfunction "VSSQ_D1") (pintype "passive"))
      (node (ref "U801") (pin "D8") (pinfunction "VSSQ_D8") (pintype "passive"))
      (node (ref "U801") (pin "E1") (pinfunction "VSS_E1") (pintype "passive"))
      (node (ref "U801") (pin "E2") (pinfunction "VSSQ_E2") (pintype "passive"))
      (node (ref "U801") (pin "E8") (pinfunction "VSSQ_E8") (pintype "passive"))
      (node (ref "U801") (pin "F9") (pinfunction "VSSQ_F9") (pintype "passive"))
      (node (ref "U801") (pin "G1") (pinfunction "VSSQ_G1") (pintype "passive"))
      (node (ref "U801") (pin "G8") (pinfunction "VSS_G8") (pintype "passive"))
      (node (ref "U801") (pin "G9") (pinfunction "VSSQ_G9") (pintype "passive"))
      (node (ref "U801") (pin "J2") (pinfunction "VSS_J2") (pintype "passive"))
      (node (ref "U801") (pin "J8") (pinfunction "VSS_J8") (pintype "passive"))
      (node (ref "U801") (pin "M1") (pinfunction "VSS_M1") (pintype "passive"))
      (node (ref "U801") (pin "M9") (pinfunction "VSS_M9") (pintype "passive"))
      (node (ref "U801") (pin "P1") (pinfunction "VSS_P1") (pintype "passive"))
      (node (ref "U801") (pin "P9") (pinfunction "VSS_P9") (pintype "passive"))
      (node (ref "U801") (pin "T1") (pinfunction "VSS_T1") (pintype "passive"))
      (node (ref "U801") (pin "T9") (pinfunction "VSS_T9") (pintype "passive"))
    )
    (net (code "75") (name "DP0.675VS_REF") (class "Default")
      (node (ref "C800") (pin "1") (pinfunction "1_1") (pintype "passive"))
      (node (ref "C801") (pin "2") (pinfunction "2_2") (pintype "passive"))
      (node (ref "C824") (pin "1") (pinfunction "1_1") (pintype "passive"))
      (node (ref "C825") (pin "2") (pinfunction "2_2") (pintype "passive"))
      (node (ref "U800") (pin "H1") (pinfunction "VREFDQ_H1") (pintype "passive"))
      (node (ref "U800") (pin "M8") (pinfunction "VREFCA_M8") (pintype "passive"))
      (node (ref "U801") (pin "H1") (pinfunction "VREFDQ_H1") (pintype "passive"))
      (node (ref "U801") (pin "M8") (pinfunction "VREFCA_M8") (pintype "passive"))
    )
    (net (code "76") (name "DP1.35VS") (class "Default")
      (node (ref "C800") (pin "2") (pinfunction "2_2") (pintype "passive"))
      (node (ref "C802") (pin "2") (pinfunction "2_2") (pintype "passive"))
      (node (ref "C803") (pin "2") (pinfunction "2_2") (pintype "passive"))
      (node (ref "C804") (pin "2") (pinfunction "2_2") (pintype "passive"))
      (node (ref "C805") (pin "2") (pinfunction "2_2") (pintype "passive"))
      (node (ref "C806") (pin "2") (pinfunction "2_2") (pintype "passive"))
      (node (ref "C807") (pin "2") (pinfunction "2_2") (pintype "passive"))
      (node (ref "C808") (pin "2") (pinfunction "2_2") (pintype "passive"))
      (node (ref "C809") (pin "2") (pinfunction "2_2") (pintype "passive"))
      (node (ref "C810") (pin "2") (pinfunction "2_2") (pintype "passive"))
      (node (ref "C811") (pin "2") (pinfunction "2_2") (pintype "passive"))
      (node (ref "C812") (pin "2") (pinfunction "2_2") (pintype "passive"))
      (node (ref "C813") (pin "2") (pinfunction "2_2") (pintype "passive"))
      (node (ref "C814") (pin "2") (pinfunction "2_2") (pintype "passive"))
      (node (ref "C815") (pin "2") (pinfunction "2_2") (pintype "passive"))
      (node (ref "C816") (pin "2") (pinfunction "2_2") (pintype "passive"))
      (node (ref "C817") (pin "2") (pinfunction "2_2") (pintype "passive"))
      (node (ref "C818") (pin "2") (pinfunction "2_2") (pintype "passive"))
      (node (ref "C819") (pin "2") (pinfunction "2_2") (pintype "passive"))
      (node (ref "C820") (pin "2") (pinfunction "2_2") (pintype "passive"))
      (node (ref "C821") (pin "2") (pinfunction "2_2") (pintype "passive"))
      (node (ref "C822") (pin "2") (pinfunction "2_2") (pintype "passive"))
      (node (ref "C823") (pin "2") (pinfunction "2_2") (pintype "passive"))
      (node (ref "C824") (pin "2") (pinfunction "2_2") (pintype "passive"))
      (node (ref "C826") (pin "2") (pinfunction "2_2") (pintype "passive"))
      (node (ref "C827") (pin "2") (pinfunction "2_2") (pintype "passive"))
      (node (ref "C828") (pin "2") (pinfunction "2_2") (pintype "passive"))
      (node (ref "C829") (pin "2") (pinfunction "2_2") (pintype "passive"))
      (node (ref "C830") (pin "2") (pinfunction "2_2") (pintype "passive"))
      (node (ref "C831") (pin "2") (pinfunction "2_2") (pintype "passive"))
      (node (ref "C832") (pin "2") (pinfunction "2_2") (pintype "passive"))
      (node (ref "C833") (pin "2") (pinfunction "2_2") (pintype "passive"))
      (node (ref "C834") (pin "2") (pinfunction "2_2") (pintype "passive"))
      (node (ref "C835") (pin "2") (pinfunction "2_2") (pintype "passive"))
      (node (ref "C836") (pin "2") (pinfunction "2_2") (pintype "passive"))
      (node (ref "C837") (pin "2") (pinfunction "2_2") (pintype "passive"))
      (node (ref "C838") (pin "2") (pinfunction "2_2") (pintype "passive"))
      (node (ref "C839") (pin "2") (pinfunction "2_2") (pintype "passive"))
      (node (ref "C840") (pin "2") (pinfunction "2_2") (pintype "passive"))
      (node (ref "C841") (pin "2") (pinfunction "2_2") (pintype "passive"))
      (node (ref "C842") (pin "2") (pinfunction "2_2") (pintype "passive"))
      (node (ref "C843") (pin "2") (pinfunction "2_2") (pintype "passive"))
      (node (ref "C844") (pin "2") (pinfunction "2_2") (pintype "passive"))
      (node (ref "C845") (pin "2") (pinfunction "2_2") (pintype "passive"))
      (node (ref "C846") (pin "2") (pinfunction "2_2") (pintype "passive"))
      (node (ref "C847") (pin "2") (pinfunction "2_2") (pintype "passive"))
      (node (ref "U800") (pin "A1") (pinfunction "VDDQ_A1") (pintype "passive"))
      (node (ref "U800") (pin "A8") (pinfunction "VDDQ_A8") (pintype "passive"))
      (node (ref "U800") (pin "B2") (pinfunction "VDD_B2") (pintype "passive"))
      (node (ref "U800") (pin "C1") (pinfunction "VDDQ_C1") (pintype "passive"))
      (node (ref "U800") (pin "C9") (pinfunction "VDDQ_C9") (pintype "passive"))
      (node (ref "U800") (pin "D2") (pinfunction "VDDQ_D2") (pintype "passive"))
      (node (ref "U800") (pin "D9") (pinfunction "VDD_D9") (pintype "passive"))
      (node (ref "U800") (pin "E9") (pinfunction "VDDQ_E9") (pintype "passive"))
      (node (ref "U800") (pin "F1") (pinfunction "VDDQ_F1") (pintype "passive"))
      (node (ref "U800") (pin "G7") (pinfunction "VDD_G7") (pintype "passive"))
      (node (ref "U800") (pin "H2") (pinfunction "VDDQ_H2") (pintype "passive"))
      (node (ref "U800") (pin "H9") (pinfunction "VDDQ_H9") (pintype "passive"))
      (node (ref "U800") (pin "K2") (pinfunction "VDD_K2") (pintype "passive"))
      (node (ref "U800") (pin "K8") (pinfunction "VDD_K8") (pintype "passive"))
      (node (ref "U800") (pin "N1") (pinfunction "VDD_N1") (pintype "passive"))
      (node (ref "U800") (pin "N9") (pinfunction "VDD_N9") (pintype "passive"))
      (node (ref "U800") (pin "R1") (pinfunction "VDD_R1") (pintype "passive"))
      (node (ref "U800") (pin "R9") (pinfunction "VDD_R9") (pintype "passive"))
      (node (ref "U801") (pin "A1") (pinfunction "VDDQ_A1") (pintype "passive"))
      (node (ref "U801") (pin "A8") (pinfunction "VDDQ_A8") (pintype "passive"))
      (node (ref "U801") (pin "B2") (pinfunction "VDD_B2") (pintype "passive"))
      (node (ref "U801") (pin "C1") (pinfunction "VDDQ_C1") (pintype "passive"))
      (node (ref "U801") (pin "C9") (pinfunction "VDDQ_C9") (pintype "passive"))
      (node (ref "U801") (pin "D2") (pinfunction "VDDQ_D2") (pintype "passive"))
      (node (ref "U801") (pin "D9") (pinfunction "VDD_D9") (pintype "passive"))
      (node (ref "U801") (pin "E9") (pinfunction "VDDQ_E9") (pintype "passive"))
      (node (ref "U801") (pin "F1") (pinfunction "VDDQ_F1") (pintype "passive"))
      (node (ref "U801") (pin "G7") (pinfunction "VDD_G7") (pintype "passive"))
      (node (ref "U801") (pin "H2") (pinfunction "VDDQ_H2") (pintype "passive"))
      (node (ref "U801") (pin "H9") (pinfunction "VDDQ_H9") (pintype "passive"))
      (node (ref "U801") (pin "K2") (pinfunction "VDD_K2") (pintype "passive"))
      (node (ref "U801") (pin "K8") (pinfunction "VDD_K8") (pintype "passive"))
      (node (ref "U801") (pin "N1") (pinfunction "VDD_N1") (pintype "passive"))
      (node (ref "U801") (pin "N9") (pinfunction "VDD_N9") (pintype "passive"))
      (node (ref "U801") (pin "R1") (pinfunction "VDD_R1") (pintype "passive"))
      (node (ref "U801") (pin "R9") (pinfunction "VDD_R9") (pintype "passive"))
    )
    (net (code "77") (name "unconnected-(U800C-NC-PadJ1)") (class "Default")
      (node (ref "U800") (pin "J1") (pinfunction "NC_J1") (pintype "passive+no_connect"))
    )
    (net (code "78") (name "unconnected-(U800C-NC-PadJ9)") (class "Default")
      (node (ref "U800") (pin "J9") (pinfunction "NC_J9") (pintype "passive+no_connect"))
    )
    (net (code "79") (name "unconnected-(U800C-NC-PadL1)") (class "Default")
      (node (ref "U800") (pin "L1") (pinfunction "NC_L1") (pintype "passive+no_connect"))
    )
    (net (code "80") (name "unconnected-(U800C-NC-PadL9)") (class "Default")
      (node (ref "U800") (pin "L9") (pinfunction "NC_L9") (pintype "passive+no_connect"))
    )
    (net (code "81") (name "unconnected-(U800C-NC-PadM7)") (class "Default")
      (node (ref "U800") (pin "M7") (pinfunction "NC_M7") (pintype "passive+no_connect"))
    )
    (net (code "82") (name "unconnected-(U801C-NC-PadJ1)") (class "Default")
      (node (ref "U801") (pin "J1") (pinfunction "NC_J1") (pintype "passive+no_connect"))
    )
    (net (code "83") (name "unconnected-(U801C-NC-PadJ9)") (class "Default")
      (node (ref "U801") (pin "J9") (pinfunction "NC_J9") (pintype "passive+no_connect"))
    )
    (net (code "84") (name "unconnected-(U801C-NC-PadL1)") (class "Default")
      (node (ref "U801") (pin "L1") (pinfunction "NC_L1") (pintype "passive+no_connect"))
    )
    (net (code "85") (name "unconnected-(U801C-NC-PadL9)") (class "Default")
      (node (ref "U801") (pin "L9") (pinfunction "NC_L9") (pintype "passive+no_connect"))
    )
    (net (code "86") (name "unconnected-(U801C-NC-PadM7)") (class "Default")
      (node (ref "U801") (pin "M7") (pinfunction "NC_M7") (pintype "passive+no_connect"))
    )
  )
)
